# SPI_Buffer.net
KiCad netlist of a schematic drawn in Altium Designer
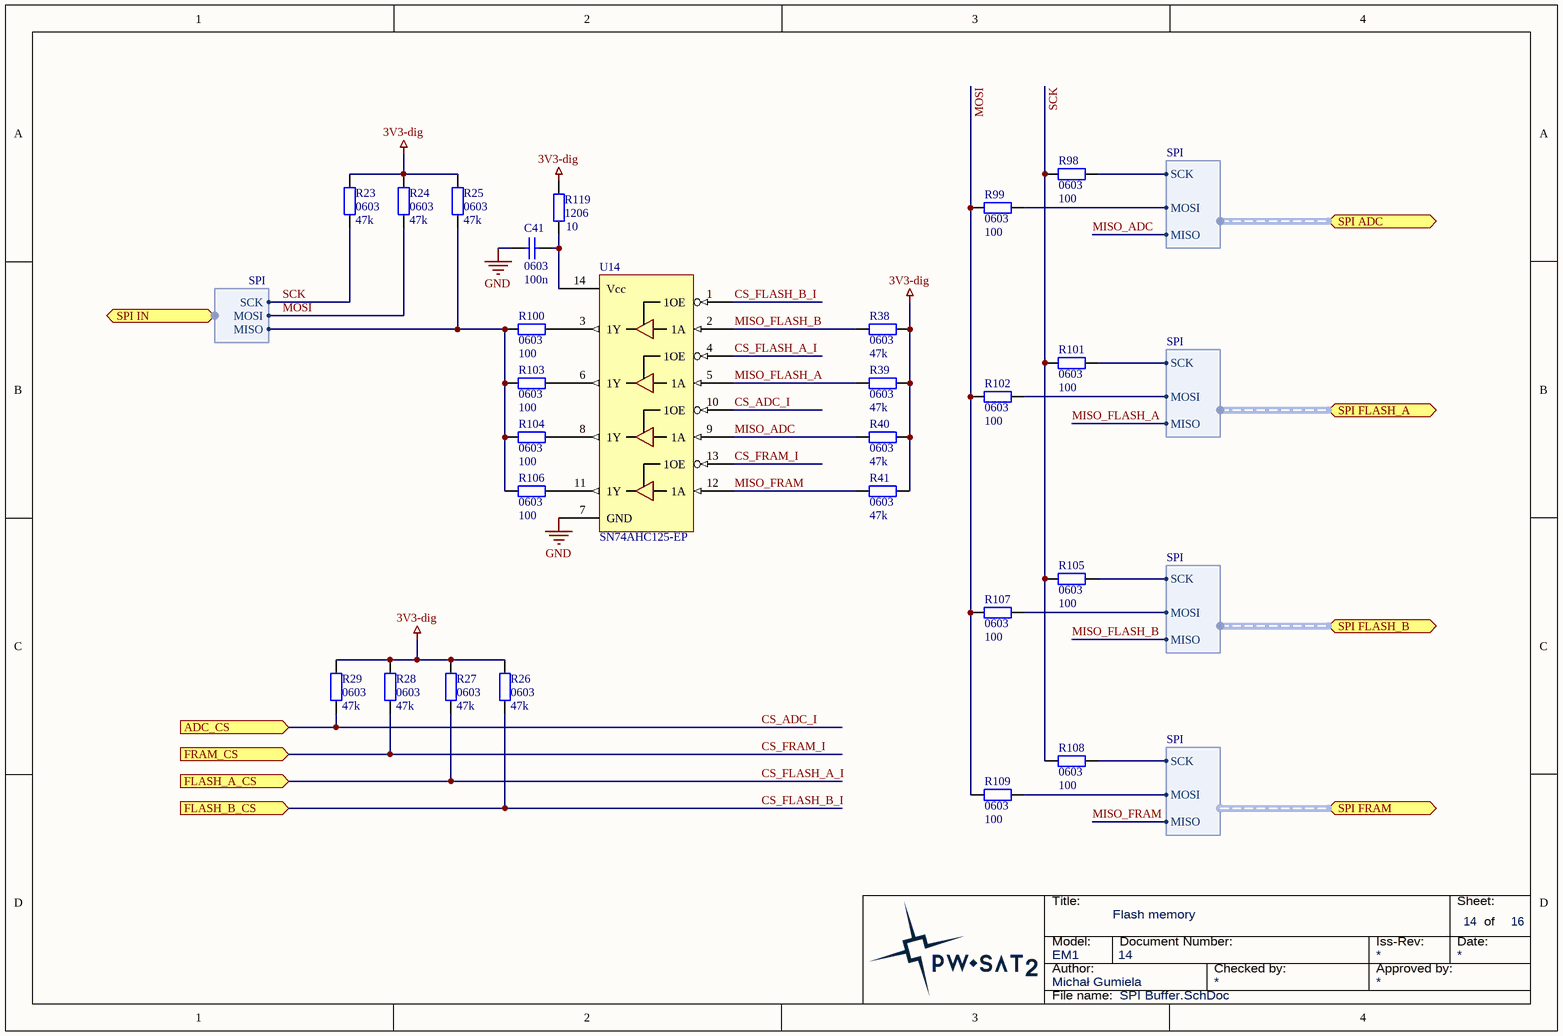
[diagram p0: SPI Buffer.SchDoc]

(export (version "E")
  (design (tool "Eeschema 10.0.6"))
  (components
    (comp (ref "C41")
      (value "0603")
      (footprint "SMD_Capacitor_0603")
      (description "Capacitor")
      (fields (field (name "ALTIUM_VALUE") "100n") (field (name "PUBLISHER") "Altium Limited"))
      (libsource (lib "Miscellaneous Devices") (part "Cap"))
    )
    (comp (ref "R23")
      (value "0603")
      (footprint "SMD_Resistor_0603")
      (description "Resistor")
      (fields (field (name "ALTIUM_VALUE") "47k") (field (name "PUBLISHER") "Altium Limited"))
      (libsource (lib "") (part "Res2_3"))
    )
    (comp (ref "R24")
      (value "0603")
      (footprint "SMD_Resistor_0603")
      (description "Resistor")
      (fields (field (name "ALTIUM_VALUE") "47k") (field (name "PUBLISHER") "Altium Limited"))
      (libsource (lib "") (part "Res2_3"))
    )
    (comp (ref "R25")
      (value "0603")
      (footprint "SMD_Resistor_0603")
      (description "Resistor")
      (fields (field (name "ALTIUM_VALUE") "47k") (field (name "PUBLISHER") "Altium Limited"))
      (libsource (lib "") (part "Res2_3"))
    )
    (comp (ref "R26")
      (value "0603")
      (footprint "SMD_Resistor_0603")
      (description "Resistor")
      (fields (field (name "ALTIUM_VALUE") "47k") (field (name "PUBLISHER") "Altium Limited"))
      (libsource (lib "") (part "Res2_2"))
    )
    (comp (ref "R27")
      (value "0603")
      (footprint "SMD_Resistor_0603")
      (description "Resistor")
      (fields (field (name "ALTIUM_VALUE") "47k") (field (name "PUBLISHER") "Altium Limited"))
      (libsource (lib "") (part "Res2_2"))
    )
    (comp (ref "R28")
      (value "0603")
      (footprint "SMD_Resistor_0603")
      (description "Resistor")
      (fields (field (name "ALTIUM_VALUE") "47k") (field (name "PUBLISHER") "Altium Limited"))
      (libsource (lib "") (part "Res2_2"))
    )
    (comp (ref "R29")
      (value "0603")
      (footprint "SMD_Resistor_0603")
      (description "Resistor")
      (fields (field (name "ALTIUM_VALUE") "47k") (field (name "PUBLISHER") "Altium Limited"))
      (libsource (lib "") (part "Res2_2"))
    )
    (comp (ref "R38")
      (value "0603")
      (footprint "SMD_Resistor_0603")
      (description "Resistor")
      (fields (field (name "ALTIUM_VALUE") "47k") (field (name "PUBLISHER") "Altium Limited"))
      (libsource (lib "Miscellaneous Devices") (part "Res2"))
    )
    (comp (ref "R39")
      (value "0603")
      (footprint "SMD_Resistor_0603")
      (description "Resistor")
      (fields (field (name "ALTIUM_VALUE") "47k") (field (name "PUBLISHER") "Altium Limited"))
      (libsource (lib "Miscellaneous Devices") (part "Res2"))
    )
    (comp (ref "R40")
      (value "0603")
      (footprint "SMD_Resistor_0603")
      (description "Resistor")
      (fields (field (name "ALTIUM_VALUE") "47k") (field (name "PUBLISHER") "Altium Limited"))
      (libsource (lib "Miscellaneous Devices") (part "Res2"))
    )
    (comp (ref "R41")
      (value "0603")
      (footprint "SMD_Resistor_0603")
      (description "Resistor")
      (fields (field (name "ALTIUM_VALUE") "47k") (field (name "PUBLISHER") "Altium Limited"))
      (libsource (lib "Miscellaneous Devices") (part "Res2"))
    )
    (comp (ref "R98")
      (value "0603")
      (footprint "SMD_Resistor_0603")
      (description "Resistor")
      (fields (field (name "ALTIUM_VALUE") "100") (field (name "PUBLISHER") "Altium Limited"))
      (libsource (lib "") (part "Res2_2"))
    )
    (comp (ref "R99")
      (value "0603")
      (footprint "SMD_Resistor_0603")
      (description "Resistor")
      (fields (field (name "ALTIUM_VALUE") "100") (field (name "PUBLISHER") "Altium Limited"))
      (libsource (lib "") (part "Res2_2"))
    )
    (comp (ref "R100")
      (value "0603")
      (footprint "SMD_Resistor_0603")
      (description "Resistor")
      (fields (field (name "ALTIUM_VALUE") "100") (field (name "PUBLISHER") "Altium Limited"))
      (libsource (lib "") (part "Res2_2"))
    )
    (comp (ref "R101")
      (value "0603")
      (footprint "SMD_Resistor_0603")
      (description "Resistor")
      (fields (field (name "ALTIUM_VALUE") "100") (field (name "PUBLISHER") "Altium Limited"))
      (libsource (lib "") (part "Res2_2"))
    )
    (comp (ref "R102")
      (value "0603")
      (footprint "SMD_Resistor_0603")
      (description "Resistor")
      (fields (field (name "ALTIUM_VALUE") "100") (field (name "PUBLISHER") "Altium Limited"))
      (libsource (lib "") (part "Res2_2"))
    )
    (comp (ref "R103")
      (value "0603")
      (footprint "SMD_Resistor_0603")
      (description "Resistor")
      (fields (field (name "ALTIUM_VALUE") "100") (field (name "PUBLISHER") "Altium Limited"))
      (libsource (lib "") (part "Res2_2"))
    )
    (comp (ref "R104")
      (value "0603")
      (footprint "SMD_Resistor_0603")
      (description "Resistor")
      (fields (field (name "ALTIUM_VALUE") "100") (field (name "PUBLISHER") "Altium Limited"))
      (libsource (lib "") (part "Res2_2"))
    )
    (comp (ref "R105")
      (value "0603")
      (footprint "SMD_Resistor_0603")
      (description "Resistor")
      (fields (field (name "ALTIUM_VALUE") "100") (field (name "PUBLISHER") "Altium Limited"))
      (libsource (lib "") (part "Res2_2"))
    )
    (comp (ref "R106")
      (value "0603")
      (footprint "SMD_Resistor_0603")
      (description "Resistor")
      (fields (field (name "ALTIUM_VALUE") "100") (field (name "PUBLISHER") "Altium Limited"))
      (libsource (lib "") (part "Res2_2"))
    )
    (comp (ref "R107")
      (value "0603")
      (footprint "SMD_Resistor_0603")
      (description "Resistor")
      (fields (field (name "ALTIUM_VALUE") "100") (field (name "PUBLISHER") "Altium Limited"))
      (libsource (lib "") (part "Res2_2"))
    )
    (comp (ref "R108")
      (value "0603")
      (footprint "SMD_Resistor_0603")
      (description "Resistor")
      (fields (field (name "ALTIUM_VALUE") "100") (field (name "PUBLISHER") "Altium Limited"))
      (libsource (lib "") (part "Res2_2"))
    )
    (comp (ref "R109")
      (value "0603")
      (footprint "SMD_Resistor_0603")
      (description "Resistor")
      (fields (field (name "ALTIUM_VALUE") "100") (field (name "PUBLISHER") "Altium Limited"))
      (libsource (lib "") (part "Res2_2"))
    )
    (comp (ref "R119")
      (value "1206")
      (footprint "SMD_Resistor_1206")
      (description "Resistor")
      (fields (field (name "ALTIUM_VALUE") "10") (field (name "PUBLISHER") "Altium Limited"))
      (libsource (lib "") (part "Res2_1"))
    )
    (comp (ref "U14")
      (value "SN74AHC125-EP")
      (footprint "TSSOP14_L")
      (description "QUADRUPLE BUS BUFFER GATE  WITH 3-STATE OUTPUTS")
      (libsource (lib "microcircuits_miscellaneous") (part "SN74AHC125-EP"))
    )
  )
  (nets
    (net (code "2") (name "/CS_ADC_I") (class "Default")
      (node (ref "R29") (pin "1") (pinfunction "1_1") (pintype "passive"))
      (node (ref "U14") (pin "10") (pinfunction "1OE_10") (pintype "input"))
    )
    (net (code "3") (name "/CS_FLASH_A_I") (class "Default")
      (node (ref "R27") (pin "1") (pinfunction "1_1") (pintype "passive"))
      (node (ref "U14") (pin "4") (pinfunction "1OE_4") (pintype "input"))
    )
    (net (code "4") (name "/CS_FLASH_B_I") (class "Default")
      (node (ref "R26") (pin "1") (pinfunction "1_1") (pintype "passive"))
      (node (ref "U14") (pin "1") (pinfunction "1OE_1") (pintype "input"))
    )
    (net (code "5") (name "/CS_FRAM_I") (class "Default")
      (node (ref "R28") (pin "1") (pinfunction "1_1") (pintype "passive"))
      (node (ref "U14") (pin "13") (pinfunction "1OE_13") (pintype "input"))
    )
    (net (code "6") (name "/MISO_ADC") (class "Default")
      (node (ref "R40") (pin "2") (pinfunction "2_2") (pintype "passive"))
      (node (ref "U14") (pin "9") (pinfunction "1A_9") (pintype "input"))
    )
    (net (code "7") (name "/MISO_FLASH_A") (class "Default")
      (node (ref "R39") (pin "2") (pinfunction "2_2") (pintype "passive"))
      (node (ref "U14") (pin "5") (pinfunction "1A_5") (pintype "input"))
    )
    (net (code "8") (name "/MISO_FLASH_B") (class "Default")
      (node (ref "R38") (pin "2") (pinfunction "2_2") (pintype "passive"))
      (node (ref "U14") (pin "2") (pinfunction "1A_2") (pintype "input"))
    )
    (net (code "9") (name "/MISO_FRAM") (class "Default")
      (node (ref "R41") (pin "2") (pinfunction "2_2") (pintype "passive"))
      (node (ref "U14") (pin "12") (pinfunction "1A_12") (pintype "input"))
    )
    (net (code "10") (name "/MOSI") (class "Default")
      (node (ref "R102") (pin "1") (pinfunction "1_1") (pintype "passive"))
      (node (ref "R107") (pin "1") (pinfunction "1_1") (pintype "passive"))
      (node (ref "R109") (pin "1") (pinfunction "1_1") (pintype "passive"))
      (node (ref "R24") (pin "1") (pinfunction "1_1") (pintype "passive"))
      (node (ref "R99") (pin "1") (pinfunction "1_1") (pintype "passive"))
    )
    (net (code "11") (name "/SCK") (class "Default")
      (node (ref "R101") (pin "1") (pinfunction "1_1") (pintype "passive"))
      (node (ref "R105") (pin "1") (pinfunction "1_1") (pintype "passive"))
      (node (ref "R108") (pin "1") (pinfunction "1_1") (pintype "passive"))
      (node (ref "R23") (pin "1") (pinfunction "1_1") (pintype "passive"))
      (node (ref "R98") (pin "1") (pinfunction "1_1") (pintype "passive"))
    )
    (net (code "13") (name "3V3-dig") (class "Default")
      (node (ref "R119") (pin "1") (pinfunction "1_1") (pintype "passive"))
      (node (ref "R23") (pin "2") (pinfunction "2_2") (pintype "passive"))
      (node (ref "R24") (pin "2") (pinfunction "2_2") (pintype "passive"))
      (node (ref "R25") (pin "2") (pinfunction "2_2") (pintype "passive"))
      (node (ref "R26") (pin "2") (pinfunction "2_2") (pintype "passive"))
      (node (ref "R27") (pin "2") (pinfunction "2_2") (pintype "passive"))
      (node (ref "R28") (pin "2") (pinfunction "2_2") (pintype "passive"))
      (node (ref "R29") (pin "2") (pinfunction "2_2") (pintype "passive"))
      (node (ref "R38") (pin "1") (pinfunction "1_1") (pintype "passive"))
      (node (ref "R39") (pin "1") (pinfunction "1_1") (pintype "passive"))
      (node (ref "R40") (pin "1") (pinfunction "1_1") (pintype "passive"))
      (node (ref "R41") (pin "1") (pinfunction "1_1") (pintype "passive"))
    )
    (net (code "14") (name "GND") (class "Default")
      (node (ref "C41") (pin "2") (pinfunction "2_2") (pintype "passive"))
      (node (ref "U14") (pin "7") (pinfunction "GND_7") (pintype "power_in"))
    )
    (net (code "15") (name "Net-(R100-Pad1)") (class "Default")
      (node (ref "R100") (pin "1") (pinfunction "1_1") (pintype "passive"))
      (node (ref "R103") (pin "1") (pinfunction "1_1") (pintype "passive"))
      (node (ref "R104") (pin "1") (pinfunction "1_1") (pintype "passive"))
      (node (ref "R106") (pin "1") (pinfunction "1_1") (pintype "passive"))
      (node (ref "R25") (pin "1") (pinfunction "1_1") (pintype "passive"))
    )
    (net (code "16") (name "Net-(R100-Pad2)") (class "Default")
      (node (ref "R100") (pin "2") (pinfunction "2_2") (pintype "passive"))
      (node (ref "U14") (pin "3") (pinfunction "1Y_3") (pintype "output"))
    )
    (net (code "17") (name "Net-(R103-Pad2)") (class "Default")
      (node (ref "R103") (pin "2") (pinfunction "2_2") (pintype "passive"))
      (node (ref "U14") (pin "6") (pinfunction "1Y_6") (pintype "output"))
    )
    (net (code "18") (name "Net-(R104-Pad2)") (class "Default")
      (node (ref "R104") (pin "2") (pinfunction "2_2") (pintype "passive"))
      (node (ref "U14") (pin "8") (pinfunction "1Y_8") (pintype "output"))
    )
    (net (code "19") (name "Net-(R106-Pad2)") (class "Default")
      (node (ref "R106") (pin "2") (pinfunction "2_2") (pintype "passive"))
      (node (ref "U14") (pin "11") (pinfunction "1Y_11") (pintype "output"))
    )
    (net (code "20") (name "Net-(U14-Vcc)") (class "Default")
      (node (ref "C41") (pin "1") (pinfunction "1_1") (pintype "passive"))
      (node (ref "R119") (pin "2") (pinfunction "2_2") (pintype "passive"))
      (node (ref "U14") (pin "14") (pinfunction "Vcc_14") (pintype "power_in"))
    )
    (net (code "21") (name "unconnected-(R98-Pad2)") (class "Default")
      (node (ref "R98") (pin "2") (pinfunction "2_2") (pintype "passive"))
    )
    (net (code "22") (name "unconnected-(R99-Pad2)") (class "Default")
      (node (ref "R99") (pin "2") (pinfunction "2_2") (pintype "passive"))
    )
    (net (code "23") (name "unconnected-(R101-Pad2)") (class "Default")
      (node (ref "R101") (pin "2") (pinfunction "2_2") (pintype "passive"))
    )
    (net (code "24") (name "unconnected-(R102-Pad2)") (class "Default")
      (node (ref "R102") (pin "2") (pinfunction "2_2") (pintype "passive"))
    )
    (net (code "25") (name "unconnected-(R105-Pad2)") (class "Default")
      (node (ref "R105") (pin "2") (pinfunction "2_2") (pintype "passive"))
    )
    (net (code "26") (name "unconnected-(R107-Pad2)") (class "Default")
      (node (ref "R107") (pin "2") (pinfunction "2_2") (pintype "passive"))
    )
    (net (code "27") (name "unconnected-(R108-Pad2)") (class "Default")
      (node (ref "R108") (pin "2") (pinfunction "2_2") (pintype "passive"))
    )
    (net (code "28") (name "unconnected-(R109-Pad2)") (class "Default")
      (node (ref "R109") (pin "2") (pinfunction "2_2") (pintype "passive"))
    )
  )
)
